# UPS.net
KiCad netlist of a schematic drawn in EAGLE
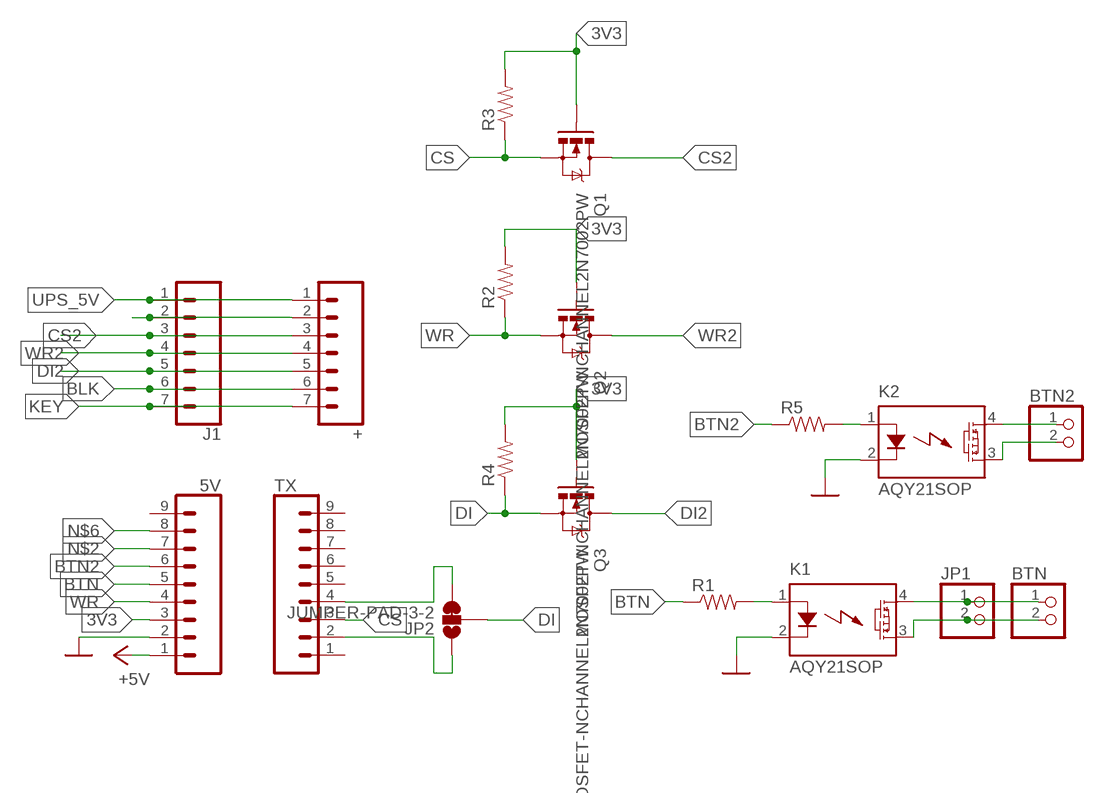
[diagram p0: schematic, sheet 1]

(export (version "E")
  (design (tool "Eeschema 10.0.6"))
  (components
    (comp (ref "+")
      (value "CONN_07")
      (footprint "eagle-import:1X07")
      (libsource (lib "eagle-import") (part "CONN_07"))
    )
    (comp (ref "5V")
      (value "CONN_09")
      (footprint "eagle-import:1X09")
      (libsource (lib "eagle-import") (part "CONN_09"))
    )
    (comp (ref "BTN")
      (value "PINHD-1X2")
      (footprint "eagle-import:1X02")
      (libsource (lib "eagle-import") (part "PINHD-1X2"))
    )
    (comp (ref "BTN2")
      (value "PINHD-1X2")
      (footprint "eagle-import:1X02")
      (libsource (lib "eagle-import") (part "PINHD-1X2"))
    )
    (comp (ref "J1")
      (value "CONN_07")
      (footprint "eagle-import:1X07")
      (libsource (lib "eagle-import") (part "CONN_07"))
    )
    (comp (ref "JP1")
      (value "PINHD-1X2")
      (footprint "eagle-import:1X02")
      (libsource (lib "eagle-import") (part "PINHD-1X2"))
    )
    (comp (ref "JP2")
      (value "JUMPER-PAD-3-2")
      (footprint "eagle-import:PAD-JUMPER-3-2OF3_NC_BY_TRACE_YES_SILK_FULL_BOX")
      (libsource (lib "eagle-import") (part "JUMPER-PAD-3-2OF3_NC_BY_TRACE_SMALL"))
    )
    (comp (ref "K1")
      (value "AQY21SOP")
      (footprint "eagle-import:SOP04")
      (libsource (lib "eagle-import") (part "AQYSOP21"))
    )
    (comp (ref "K2")
      (value "AQY21SOP")
      (footprint "eagle-import:SOP04")
      (libsource (lib "eagle-import") (part "AQYSOP21"))
    )
    (comp (ref "Q1")
      (value "MOSFET-NCHANNEL2N7002PW")
      (footprint "eagle-import:SOT323")
      (libsource (lib "eagle-import") (part "MOSFET-NCHANNEL2N7002PW"))
    )
    (comp (ref "Q2")
      (value "MOSFET-NCHANNEL2N7002PW")
      (footprint "eagle-import:SOT323")
      (libsource (lib "eagle-import") (part "MOSFET-NCHANNEL2N7002PW"))
    )
    (comp (ref "Q3")
      (value "MOSFET-NCHANNEL2N7002PW")
      (footprint "eagle-import:SOT323")
      (libsource (lib "eagle-import") (part "MOSFET-NCHANNEL2N7002PW"))
    )
    (comp (ref "R1")
      (value "RESISTOR0805-RES")
      (footprint "eagle-import:0805")
      (libsource (lib "eagle-import") (part "RESISTOR0805-RES"))
    )
    (comp (ref "R2")
      (value "RESISTOR0805-RES")
      (footprint "eagle-import:0805")
      (libsource (lib "eagle-import") (part "RESISTOR0805-RES"))
    )
    (comp (ref "R3")
      (value "RESISTOR0805-RES")
      (footprint "eagle-import:0805")
      (libsource (lib "eagle-import") (part "RESISTOR0805-RES"))
    )
    (comp (ref "R4")
      (value "RESISTOR0805-RES")
      (footprint "eagle-import:0805")
      (libsource (lib "eagle-import") (part "RESISTOR0805-RES"))
    )
    (comp (ref "R5")
      (value "RESISTOR0805-RES")
      (footprint "eagle-import:0805")
      (libsource (lib "eagle-import") (part "RESISTOR0805-RES"))
    )
    (comp (ref "TX")
      (value "CONN_09")
      (footprint "eagle-import:1X09")
      (libsource (lib "eagle-import") (part "CONN_09"))
    )
  )
  (nets
    (net (code "1") (name "+5V") (class "Default")
      (node (ref "5V") (pin "1") (pinfunction "1_1") (pintype "passive"))
    )
    (net (code "2") (name "3V3") (class "Default")
      (node (ref "5V") (pin "3") (pinfunction "3_3") (pintype "passive"))
      (node (ref "Q1") (pin "1") (pinfunction "G_1") (pintype "passive"))
      (node (ref "Q2") (pin "1") (pinfunction "G_1") (pintype "passive"))
      (node (ref "Q3") (pin "1") (pinfunction "G_1") (pintype "passive"))
      (node (ref "R2") (pin "2") (pinfunction "2_2") (pintype "passive"))
      (node (ref "R3") (pin "2") (pinfunction "2_2") (pintype "passive"))
      (node (ref "R4") (pin "2") (pinfunction "2_2") (pintype "passive"))
    )
    (net (code "3") (name "BLK") (class "Default")
      (node (ref "+") (pin "6") (pinfunction "6_6") (pintype "passive"))
      (node (ref "J1") (pin "6") (pinfunction "6_6") (pintype "passive"))
    )
    (net (code "4") (name "BTN") (class "Default")
      (node (ref "5V") (pin "5") (pinfunction "5_5") (pintype "passive"))
      (node (ref "R1") (pin "1") (pinfunction "1_1") (pintype "passive"))
    )
    (net (code "5") (name "BTN2") (class "Default")
      (node (ref "5V") (pin "6") (pinfunction "6_6") (pintype "passive"))
      (node (ref "R5") (pin "1") (pinfunction "1_1") (pintype "passive"))
    )
    (net (code "6") (name "CS") (class "Default")
      (node (ref "Q1") (pin "2") (pinfunction "S_2") (pintype "passive"))
      (node (ref "R3") (pin "1") (pinfunction "1_1") (pintype "passive"))
      (node (ref "TX") (pin "3") (pinfunction "3_3") (pintype "passive"))
    )
    (net (code "7") (name "CS2") (class "Default")
      (node (ref "+") (pin "3") (pinfunction "3_3") (pintype "passive"))
      (node (ref "J1") (pin "3") (pinfunction "3_3") (pintype "passive"))
      (node (ref "Q1") (pin "3") (pinfunction "D_3") (pintype "passive"))
    )
    (net (code "8") (name "DI") (class "Default")
      (node (ref "JP2") (pin "2") (pinfunction "2_2") (pintype "passive"))
      (node (ref "Q3") (pin "2") (pinfunction "S_2") (pintype "passive"))
      (node (ref "R4") (pin "1") (pinfunction "1_1") (pintype "passive"))
    )
    (net (code "9") (name "DI2") (class "Default")
      (node (ref "+") (pin "5") (pinfunction "5_5") (pintype "passive"))
      (node (ref "J1") (pin "5") (pinfunction "5_5") (pintype "passive"))
      (node (ref "Q3") (pin "3") (pinfunction "D_3") (pintype "passive"))
    )
    (net (code "10") (name "GND") (class "Default")
      (node (ref "5V") (pin "2") (pinfunction "2_2") (pintype "passive"))
      (node (ref "K1") (pin "2") (pinfunction "K_2") (pintype "passive"))
      (node (ref "K2") (pin "2") (pinfunction "K_2") (pintype "passive"))
    )
    (net (code "11") (name "KEY") (class "Default")
      (node (ref "+") (pin "7") (pinfunction "7_7") (pintype "passive"))
      (node (ref "J1") (pin "7") (pinfunction "7_7") (pintype "passive"))
    )
    (net (code "12") (name "N$2") (class "Default")
      (node (ref "5V") (pin "7") (pinfunction "7_7") (pintype "passive"))
    )
    (net (code "13") (name "N$6") (class "Default")
      (node (ref "5V") (pin "8") (pinfunction "8_8") (pintype "passive"))
    )
    (net (code "14") (name "Net-(+-Pad2)") (class "Default")
      (node (ref "+") (pin "2") (pinfunction "2_2") (pintype "passive"))
      (node (ref "J1") (pin "2") (pinfunction "2_2") (pintype "passive"))
    )
    (net (code "15") (name "Net-(JP2-Pad1)") (class "Default")
      (node (ref "JP2") (pin "1") (pinfunction "1_1") (pintype "passive"))
      (node (ref "TX") (pin "2") (pinfunction "2_2") (pintype "passive"))
    )
    (net (code "16") (name "Net-(JP2-Pad3)") (class "Default")
      (node (ref "JP2") (pin "3") (pinfunction "3_3") (pintype "passive"))
      (node (ref "TX") (pin "4") (pinfunction "4_4") (pintype "passive"))
    )
    (net (code "17") (name "Net-(K1-A)") (class "Default")
      (node (ref "K1") (pin "1") (pinfunction "A_1") (pintype "passive"))
      (node (ref "R1") (pin "2") (pinfunction "2_2") (pintype "passive"))
    )
    (net (code "18") (name "Net-(K1-DS1)") (class "Default")
      (node (ref "BTN") (pin "1") (pinfunction "1_1") (pintype "passive"))
      (node (ref "JP1") (pin "1") (pinfunction "1_1") (pintype "passive"))
      (node (ref "K1") (pin "4") (pinfunction "DS1_4") (pintype "passive"))
    )
    (net (code "19") (name "Net-(K1-DS2)") (class "Default")
      (node (ref "BTN") (pin "2") (pinfunction "2_2") (pintype "passive"))
      (node (ref "JP1") (pin "2") (pinfunction "2_2") (pintype "passive"))
      (node (ref "K1") (pin "3") (pinfunction "DS2_3") (pintype "passive"))
    )
    (net (code "20") (name "Net-(K2-A)") (class "Default")
      (node (ref "K2") (pin "1") (pinfunction "A_1") (pintype "passive"))
      (node (ref "R5") (pin "2") (pinfunction "2_2") (pintype "passive"))
    )
    (net (code "21") (name "Net-(K2-DS1)") (class "Default")
      (node (ref "BTN2") (pin "1") (pinfunction "1_1") (pintype "passive"))
      (node (ref "K2") (pin "4") (pinfunction "DS1_4") (pintype "passive"))
    )
    (net (code "22") (name "Net-(K2-DS2)") (class "Default")
      (node (ref "BTN2") (pin "2") (pinfunction "2_2") (pintype "passive"))
      (node (ref "K2") (pin "3") (pinfunction "DS2_3") (pintype "passive"))
    )
    (net (code "23") (name "UPS_5V") (class "Default")
      (node (ref "+") (pin "1") (pinfunction "1_1") (pintype "passive"))
      (node (ref "J1") (pin "1") (pinfunction "1_1") (pintype "passive"))
    )
    (net (code "24") (name "WR") (class "Default")
      (node (ref "5V") (pin "4") (pinfunction "4_4") (pintype "passive"))
      (node (ref "Q2") (pin "2") (pinfunction "S_2") (pintype "passive"))
      (node (ref "R2") (pin "1") (pinfunction "1_1") (pintype "passive"))
    )
    (net (code "25") (name "WR2") (class "Default")
      (node (ref "+") (pin "4") (pinfunction "4_4") (pintype "passive"))
      (node (ref "J1") (pin "4") (pinfunction "4_4") (pintype "passive"))
      (node (ref "Q2") (pin "3") (pinfunction "D_3") (pintype "passive"))
    )
    (net (code "26") (name "unconnected-(5V-Pad9)") (class "Default")
      (node (ref "5V") (pin "9") (pinfunction "9_9") (pintype "passive"))
    )
    (net (code "27") (name "unconnected-(TX-Pad1)") (class "Default")
      (node (ref "TX") (pin "1") (pinfunction "1_1") (pintype "passive"))
    )
    (net (code "28") (name "unconnected-(TX-Pad5)") (class "Default")
      (node (ref "TX") (pin "5") (pinfunction "5_5") (pintype "passive"))
    )
    (net (code "29") (name "unconnected-(TX-Pad6)") (class "Default")
      (node (ref "TX") (pin "6") (pinfunction "6_6") (pintype "passive"))
    )
    (net (code "30") (name "unconnected-(TX-Pad7)") (class "Default")
      (node (ref "TX") (pin "7") (pinfunction "7_7") (pintype "passive"))
    )
    (net (code "31") (name "unconnected-(TX-Pad8)") (class "Default")
      (node (ref "TX") (pin "8") (pinfunction "8_8") (pintype "passive"))
    )
    (net (code "32") (name "unconnected-(TX-Pad9)") (class "Default")
      (node (ref "TX") (pin "9") (pinfunction "9_9") (pintype "passive"))
    )
  )
)
